# pico_test_w5100s_evb.net
KiCad netlist of a schematic drawn in EAGLE
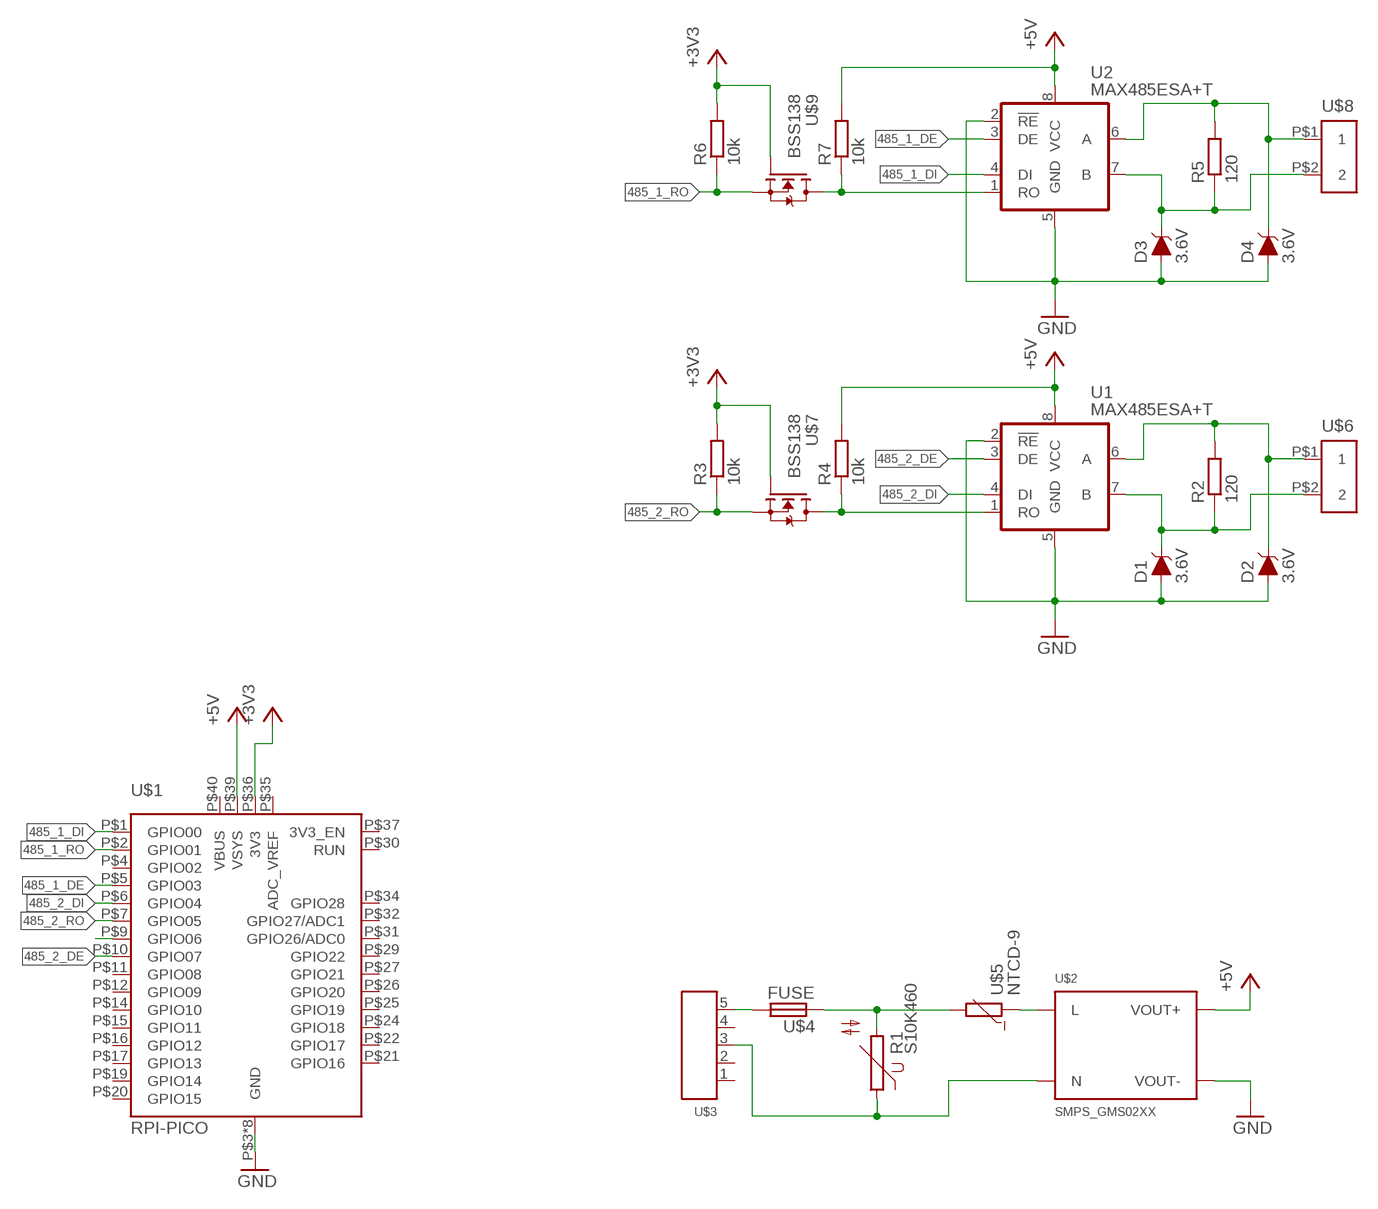
[diagram p0: schematic, sheet 1]

(export (version "E")
  (design (tool "Eeschema 10.0.6"))
  (components
    (comp (ref "D1")
      (value "3.6V")
      (footprint "eagle-import:SOD-323")
      (libsource (lib "eagle-import") (part "DIODE-ZENER-BZT52C3V6S"))
    )
    (comp (ref "D2")
      (value "3.6V")
      (footprint "eagle-import:SOD-323")
      (libsource (lib "eagle-import") (part "DIODE-ZENER-BZT52C3V6S"))
    )
    (comp (ref "D3")
      (value "3.6V")
      (footprint "eagle-import:SOD-323")
      (libsource (lib "eagle-import") (part "DIODE-ZENER-BZT52C3V6S"))
    )
    (comp (ref "D4")
      (value "3.6V")
      (footprint "eagle-import:SOD-323")
      (libsource (lib "eagle-import") (part "DIODE-ZENER-BZT52C3V6S"))
    )
    (comp (ref "R1")
      (value "S10K460")
      (footprint "eagle-import:S10K460")
      (libsource (lib "eagle-import") (part "S10K460"))
    )
    (comp (ref "R2")
      (value "120")
      (footprint "eagle-import:R0603")
      (libsource (lib "eagle-import") (part "R-EU_R0603"))
    )
    (comp (ref "R3")
      (value "10k")
      (footprint "eagle-import:R0603")
      (libsource (lib "eagle-import") (part "R-EU_R0603"))
    )
    (comp (ref "R4")
      (value "10k")
      (footprint "eagle-import:R0603")
      (libsource (lib "eagle-import") (part "R-EU_R0603"))
    )
    (comp (ref "R5")
      (value "120")
      (footprint "eagle-import:R0603")
      (libsource (lib "eagle-import") (part "R-EU_R0603"))
    )
    (comp (ref "R6")
      (value "10k")
      (footprint "eagle-import:R0603")
      (libsource (lib "eagle-import") (part "R-EU_R0603"))
    )
    (comp (ref "R7")
      (value "10k")
      (footprint "eagle-import:R0603")
      (libsource (lib "eagle-import") (part "R-EU_R0603"))
    )
    (comp (ref "U$1")
      (value "RPI-PICO")
      (footprint "eagle-import:W5100S-EVB-PICO")
      (libsource (lib "eagle-import") (part "RPI-PICO"))
    )
    (comp (ref "U$2")
      (value "SMPS_GMS02XX")
      (footprint "eagle-import:GMS02XX")
      (libsource (lib "eagle-import") (part "SMPS_GMS02XX"))
    )
    (comp (ref "U$3")
      (value "XEHDR-5")
      (footprint "eagle-import:XEHDR-5")
      (libsource (lib "eagle-import") (part "XEHDR-5"))
    )
    (comp (ref "U$4")
      (value "FUSE")
      (footprint "eagle-import:FUZEX8.5X4.5X5.08")
      (libsource (lib "eagle-import") (part "FUSE"))
    )
    (comp (ref "U$5")
      (value "NTCD-9")
      (footprint "eagle-import:NTCXD-9")
      (libsource (lib "eagle-import") (part "NTCD-9"))
    )
    (comp (ref "U$6")
      (value "XEHDR-2")
      (footprint "eagle-import:5EHDR-2")
      (libsource (lib "eagle-import") (part "XEHDR-2"))
    )
    (comp (ref "U$7")
      (value "BSS138")
      (footprint "eagle-import:SOT95P240X110-3N")
      (libsource (lib "eagle-import") (part "BSS138"))
    )
    (comp (ref "U$8")
      (value "XEHDR-2")
      (footprint "eagle-import:5EHDR-2")
      (libsource (lib "eagle-import") (part "XEHDR-2"))
    )
    (comp (ref "U$9")
      (value "BSS138")
      (footprint "eagle-import:SOT95P240X110-3N")
      (libsource (lib "eagle-import") (part "BSS138"))
    )
    (comp (ref "U1")
      (value "MAX485ESA+T")
      (footprint "eagle-import:SOIC127P600X175-8N")
      (fields (field (name "MF") "Maxim Integrated"))
      (libsource (lib "eagle-import") (part "MAX485ESA+T"))
    )
    (comp (ref "U2")
      (value "MAX485ESA+T")
      (footprint "eagle-import:SOIC127P600X175-8N")
      (fields (field (name "MF") "Maxim Integrated"))
      (libsource (lib "eagle-import") (part "MAX485ESA+T"))
    )
  )
  (nets
    (net (code "1") (name "+3V3") (class "Default")
      (node (ref "R3") (pin "2") (pinfunction "2_2") (pintype "passive"))
      (node (ref "R6") (pin "2") (pinfunction "2_2") (pintype "passive"))
      (node (ref "U$1") (pin "P$36") (pinfunction "3V3_P$36") (pintype "bidirectional"))
      (node (ref "U$7") (pin "1") (pinfunction "G_1") (pintype "passive"))
      (node (ref "U$9") (pin "1") (pinfunction "G_1") (pintype "passive"))
    )
    (net (code "2") (name "+5V") (class "Default")
      (node (ref "R4") (pin "2") (pinfunction "2_2") (pintype "passive"))
      (node (ref "R7") (pin "2") (pinfunction "2_2") (pintype "passive"))
      (node (ref "U$1") (pin "P$39") (pinfunction "VSYS_P$39") (pintype "bidirectional"))
      (node (ref "U$2") (pin "DC+") (pinfunction "VOUT+_DC+") (pintype "bidirectional"))
      (node (ref "U1") (pin "8") (pinfunction "VCC_8") (pintype "power_in"))
      (node (ref "U2") (pin "8") (pinfunction "VCC_8") (pintype "power_in"))
    )
    (net (code "3") (name "485_1_DE") (class "Default")
      (node (ref "U$1") (pin "P$5") (pinfunction "GPIO03_P$5") (pintype "bidirectional"))
      (node (ref "U2") (pin "3") (pinfunction "DE_3") (pintype "input"))
    )
    (net (code "4") (name "485_1_DI") (class "Default")
      (node (ref "U$1") (pin "P$1") (pinfunction "GPIO00_P$1") (pintype "bidirectional"))
      (node (ref "U2") (pin "4") (pinfunction "DI_4") (pintype "input"))
    )
    (net (code "5") (name "485_1_RO") (class "Default")
      (node (ref "R6") (pin "1") (pinfunction "1_1") (pintype "passive"))
      (node (ref "U$1") (pin "P$2") (pinfunction "GPIO01_P$2") (pintype "bidirectional"))
      (node (ref "U$9") (pin "2") (pinfunction "S_2") (pintype "passive"))
    )
    (net (code "6") (name "485_2_DE") (class "Default")
      (node (ref "U$1") (pin "P$10") (pinfunction "GPIO07_P$10") (pintype "bidirectional"))
      (node (ref "U1") (pin "3") (pinfunction "DE_3") (pintype "input"))
    )
    (net (code "7") (name "485_2_DI") (class "Default")
      (node (ref "U$1") (pin "P$6") (pinfunction "GPIO04_P$6") (pintype "bidirectional"))
      (node (ref "U1") (pin "4") (pinfunction "DI_4") (pintype "input"))
    )
    (net (code "8") (name "485_2_RO") (class "Default")
      (node (ref "R3") (pin "1") (pinfunction "1_1") (pintype "passive"))
      (node (ref "U$1") (pin "P$7") (pinfunction "GPIO05_P$7") (pintype "bidirectional"))
      (node (ref "U$7") (pin "2") (pinfunction "S_2") (pintype "passive"))
    )
    (net (code "9") (name "GND") (class "Default")
      (node (ref "D1") (pin "A") (pinfunction "A_A") (pintype "passive"))
      (node (ref "D2") (pin "A") (pinfunction "A_A") (pintype "passive"))
      (node (ref "D3") (pin "A") (pinfunction "A_A") (pintype "passive"))
      (node (ref "D4") (pin "A") (pinfunction "A_A") (pintype "passive"))
      (node (ref "U$1") (pin "P$13") (pinfunction "GND_P$13") (pintype "bidirectional"))
      (node (ref "U$1") (pin "P$18") (pinfunction "GND_P$18") (pintype "bidirectional"))
      (node (ref "U$1") (pin "P$23") (pinfunction "GND_P$23") (pintype "bidirectional"))
      (node (ref "U$1") (pin "P$28") (pinfunction "GND_P$28") (pintype "bidirectional"))
      (node (ref "U$1") (pin "P$3") (pinfunction "GND_P$3") (pintype "bidirectional"))
      (node (ref "U$1") (pin "P$33") (pinfunction "GND_P$33") (pintype "bidirectional"))
      (node (ref "U$1") (pin "P$38") (pinfunction "GND_P$38") (pintype "bidirectional"))
      (node (ref "U$1") (pin "P$8") (pinfunction "GND_P$8") (pintype "bidirectional"))
      (node (ref "U$2") (pin "DC-") (pinfunction "VOUT-_DC-") (pintype "bidirectional"))
      (node (ref "U1") (pin "2") (pinfunction "~{RE}_2") (pintype "input"))
      (node (ref "U1") (pin "5") (pinfunction "GND_5") (pintype "power_in"))
      (node (ref "U2") (pin "2") (pinfunction "~{RE}_2") (pintype "input"))
      (node (ref "U2") (pin "5") (pinfunction "GND_5") (pintype "power_in"))
    )
    (net (code "10") (name "Net-(U$2-L)") (class "Default")
      (node (ref "U$2") (pin "P$1") (pinfunction "L_P$1") (pintype "bidirectional"))
      (node (ref "U$5") (pin "P$1") (pinfunction "1_P$1") (pintype "passive"))
    )
    (net (code "11") (name "Net-(U$2-N)") (class "Default")
      (node (ref "R1") (pin "1") (pinfunction "1_1") (pintype "passive"))
      (node (ref "U$2") (pin "P$2") (pinfunction "N_P$2") (pintype "bidirectional"))
      (node (ref "U$3") (pin "3") (pinfunction "P$3_3") (pintype "bidirectional"))
    )
    (net (code "12") (name "Net-(U$3-P$5)") (class "Default")
      (node (ref "U$3") (pin "5") (pinfunction "P$5_5") (pintype "bidirectional"))
      (node (ref "U$4") (pin "P$2") (pinfunction "2_P$2") (pintype "passive"))
    )
    (net (code "13") (name "Net-(U$4-1)") (class "Default")
      (node (ref "R1") (pin "2") (pinfunction "2_2") (pintype "passive"))
      (node (ref "U$4") (pin "P$1") (pinfunction "1_P$1") (pintype "passive"))
      (node (ref "U$5") (pin "P$2") (pinfunction "2_P$2") (pintype "passive"))
    )
    (net (code "14") (name "Net-(U$6-1)") (class "Default")
      (node (ref "D2") (pin "C") (pinfunction "C_C") (pintype "passive"))
      (node (ref "R2") (pin "2") (pinfunction "2_2") (pintype "passive"))
      (node (ref "U$6") (pin "P$1") (pinfunction "1_P$1") (pintype "bidirectional"))
      (node (ref "U1") (pin "6") (pinfunction "A_6") (pintype "bidirectional"))
    )
    (net (code "15") (name "Net-(U$6-2)") (class "Default")
      (node (ref "D1") (pin "C") (pinfunction "C_C") (pintype "passive"))
      (node (ref "R2") (pin "1") (pinfunction "1_1") (pintype "passive"))
      (node (ref "U$6") (pin "P$2") (pinfunction "2_P$2") (pintype "bidirectional"))
      (node (ref "U1") (pin "7") (pinfunction "B_7") (pintype "bidirectional"))
    )
    (net (code "16") (name "Net-(U$7-D)") (class "Default")
      (node (ref "R4") (pin "1") (pinfunction "1_1") (pintype "passive"))
      (node (ref "U$7") (pin "3") (pinfunction "D_3") (pintype "passive"))
      (node (ref "U1") (pin "1") (pinfunction "RO_1") (pintype "output"))
    )
    (net (code "17") (name "Net-(U$8-1)") (class "Default")
      (node (ref "D4") (pin "C") (pinfunction "C_C") (pintype "passive"))
      (node (ref "R5") (pin "2") (pinfunction "2_2") (pintype "passive"))
      (node (ref "U$8") (pin "P$1") (pinfunction "1_P$1") (pintype "bidirectional"))
      (node (ref "U2") (pin "6") (pinfunction "A_6") (pintype "bidirectional"))
    )
    (net (code "18") (name "Net-(U$8-2)") (class "Default")
      (node (ref "D3") (pin "C") (pinfunction "C_C") (pintype "passive"))
      (node (ref "R5") (pin "1") (pinfunction "1_1") (pintype "passive"))
      (node (ref "U$8") (pin "P$2") (pinfunction "2_P$2") (pintype "bidirectional"))
      (node (ref "U2") (pin "7") (pinfunction "B_7") (pintype "bidirectional"))
    )
    (net (code "19") (name "Net-(U$9-D)") (class "Default")
      (node (ref "R7") (pin "1") (pinfunction "1_1") (pintype "passive"))
      (node (ref "U$9") (pin "3") (pinfunction "D_3") (pintype "passive"))
      (node (ref "U2") (pin "1") (pinfunction "RO_1") (pintype "output"))
    )
    (net (code "20") (name "unconnected-(U$1-3V3_EN-PadP$37)") (class "Default")
      (node (ref "U$1") (pin "P$37") (pinfunction "3V3_EN_P$37") (pintype "bidirectional"))
    )
    (net (code "21") (name "unconnected-(U$1-ADC_VREF-PadP$35)") (class "Default")
      (node (ref "U$1") (pin "P$35") (pinfunction "ADC_VREF_P$35") (pintype "bidirectional"))
    )
    (net (code "22") (name "unconnected-(U$1-GPIO02-PadP$4)") (class "Default")
      (node (ref "U$1") (pin "P$4") (pinfunction "GPIO02_P$4") (pintype "bidirectional"))
    )
    (net (code "23") (name "unconnected-(U$1-GPIO06-PadP$9)") (class "Default")
      (node (ref "U$1") (pin "P$9") (pinfunction "GPIO06_P$9") (pintype "bidirectional"))
    )
    (net (code "24") (name "unconnected-(U$1-GPIO08-PadP$11)") (class "Default")
      (node (ref "U$1") (pin "P$11") (pinfunction "GPIO08_P$11") (pintype "bidirectional"))
    )
    (net (code "25") (name "unconnected-(U$1-GPIO09-PadP$12)") (class "Default")
      (node (ref "U$1") (pin "P$12") (pinfunction "GPIO09_P$12") (pintype "bidirectional"))
    )
    (net (code "26") (name "unconnected-(U$1-GPIO10-PadP$14)") (class "Default")
      (node (ref "U$1") (pin "P$14") (pinfunction "GPIO10_P$14") (pintype "bidirectional"))
    )
    (net (code "27") (name "unconnected-(U$1-GPIO11-PadP$15)") (class "Default")
      (node (ref "U$1") (pin "P$15") (pinfunction "GPIO11_P$15") (pintype "bidirectional"))
    )
    (net (code "28") (name "unconnected-(U$1-GPIO12-PadP$16)") (class "Default")
      (node (ref "U$1") (pin "P$16") (pinfunction "GPIO12_P$16") (pintype "bidirectional"))
    )
    (net (code "29") (name "unconnected-(U$1-GPIO13-PadP$17)") (class "Default")
      (node (ref "U$1") (pin "P$17") (pinfunction "GPIO13_P$17") (pintype "bidirectional"))
    )
    (net (code "30") (name "unconnected-(U$1-GPIO14-PadP$19)") (class "Default")
      (node (ref "U$1") (pin "P$19") (pinfunction "GPIO14_P$19") (pintype "bidirectional"))
    )
    (net (code "31") (name "unconnected-(U$1-GPIO15-PadP$20)") (class "Default")
      (node (ref "U$1") (pin "P$20") (pinfunction "GPIO15_P$20") (pintype "bidirectional"))
    )
    (net (code "32") (name "unconnected-(U$1-GPIO16-PadP$21)") (class "Default")
      (node (ref "U$1") (pin "P$21") (pinfunction "GPIO16_P$21") (pintype "bidirectional"))
    )
    (net (code "33") (name "unconnected-(U$1-GPIO17-PadP$22)") (class "Default")
      (node (ref "U$1") (pin "P$22") (pinfunction "GPIO17_P$22") (pintype "bidirectional"))
    )
    (net (code "34") (name "unconnected-(U$1-GPIO18-PadP$24)") (class "Default")
      (node (ref "U$1") (pin "P$24") (pinfunction "GPIO18_P$24") (pintype "bidirectional"))
    )
    (net (code "35") (name "unconnected-(U$1-GPIO19-PadP$25)") (class "Default")
      (node (ref "U$1") (pin "P$25") (pinfunction "GPIO19_P$25") (pintype "bidirectional"))
    )
    (net (code "36") (name "unconnected-(U$1-GPIO20-PadP$26)") (class "Default")
      (node (ref "U$1") (pin "P$26") (pinfunction "GPIO20_P$26") (pintype "bidirectional"))
    )
    (net (code "37") (name "unconnected-(U$1-GPIO21-PadP$27)") (class "Default")
      (node (ref "U$1") (pin "P$27") (pinfunction "GPIO21_P$27") (pintype "bidirectional"))
    )
    (net (code "38") (name "unconnected-(U$1-GPIO22-PadP$29)") (class "Default")
      (node (ref "U$1") (pin "P$29") (pinfunction "GPIO22_P$29") (pintype "bidirectional"))
    )
    (net (code "39") (name "unconnected-(U$1-GPIO26{slash}ADC0-PadP$31)") (class "Default")
      (node (ref "U$1") (pin "P$31") (pinfunction "GPIO26/ADC0_P$31") (pintype "bidirectional"))
    )
    (net (code "40") (name "unconnected-(U$1-GPIO27{slash}ADC1-PadP$32)") (class "Default")
      (node (ref "U$1") (pin "P$32") (pinfunction "GPIO27/ADC1_P$32") (pintype "bidirectional"))
    )
    (net (code "41") (name "unconnected-(U$1-GPIO28-PadP$34)") (class "Default")
      (node (ref "U$1") (pin "P$34") (pinfunction "GPIO28_P$34") (pintype "bidirectional"))
    )
    (net (code "42") (name "unconnected-(U$1-RUN-PadP$30)") (class "Default")
      (node (ref "U$1") (pin "P$30") (pinfunction "RUN_P$30") (pintype "bidirectional"))
    )
    (net (code "43") (name "unconnected-(U$1-VBUS-PadP$40)") (class "Default")
      (node (ref "U$1") (pin "P$40") (pinfunction "VBUS_P$40") (pintype "bidirectional"))
    )
    (net (code "44") (name "unconnected-(U$3-P$1-Pad1)") (class "Default")
      (node (ref "U$3") (pin "1") (pinfunction "P$1_1") (pintype "bidirectional"))
    )
    (net (code "45") (name "unconnected-(U$3-P$2-Pad2)") (class "Default")
      (node (ref "U$3") (pin "2") (pinfunction "P$2_2") (pintype "bidirectional"))
    )
    (net (code "46") (name "unconnected-(U$3-P$4-Pad4)") (class "Default")
      (node (ref "U$3") (pin "4") (pinfunction "P$4_4") (pintype "bidirectional"))
    )
  )
)
